# design.net
KiCad netlist of a schematic drawn in Altium Designer
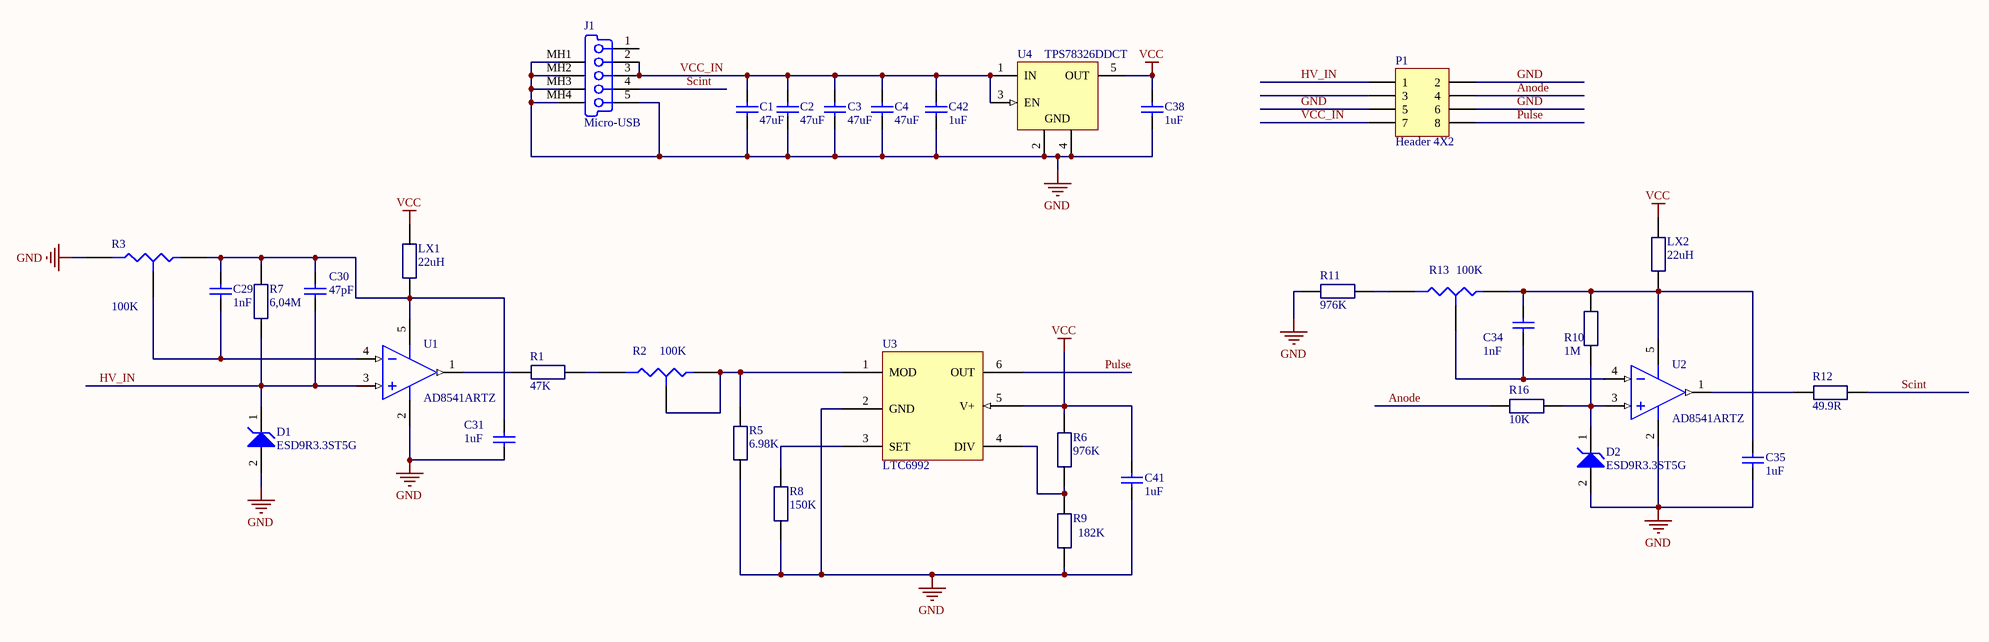
[diagram p0: Умножитель.SchDoc]

(export (version "E")
  (design (tool "Eeschema 10.0.6"))
  (components
    (comp (ref "C1")
      (value "47uF")
      (footprint "C1206")
      (description "Capacitor (Semiconductor SIM Model)")
      (fields (field (name "PUBLISHER") "Altium Limited"))
      (libsource (lib "Miscellaneous Devices") (part "Cap Semi"))
    )
    (comp (ref "C2")
      (value "47uF")
      (footprint "C1206")
      (description "Capacitor (Semiconductor SIM Model)")
      (fields (field (name "PUBLISHER") "Altium Limited"))
      (libsource (lib "Miscellaneous Devices") (part "Cap Semi"))
    )
    (comp (ref "C3")
      (value "47uF")
      (footprint "C1206")
      (description "Capacitor (Semiconductor SIM Model)")
      (fields (field (name "PUBLISHER") "Altium Limited"))
      (libsource (lib "Miscellaneous Devices") (part "Cap Semi"))
    )
    (comp (ref "C4")
      (value "47uF")
      (footprint "C1206")
      (description "Capacitor (Semiconductor SIM Model)")
      (fields (field (name "PUBLISHER") "Altium Limited"))
      (libsource (lib "Miscellaneous Devices") (part "Cap Semi"))
    )
    (comp (ref "C29")
      (value "1nF")
      (footprint "1608[0603]_CAP")
      (description "Capacitor (Semiconductor SIM Model)")
      (fields (field (name "PUBLISHER") "Altium Limited"))
      (libsource (lib "Miscellaneous Devices") (part "Cap Semi"))
    )
    (comp (ref "C30")
      (value "47pF")
      (footprint "1608[0603]_CAP")
      (description "Capacitor (Semiconductor SIM Model)")
      (fields (field (name "PUBLISHER") "Altium Limited"))
      (libsource (lib "Miscellaneous Devices") (part "Cap Semi"))
    )
    (comp (ref "C31")
      (value "1uF")
      (footprint "1608[0603]_CAP")
      (description "Capacitor (Semiconductor SIM Model)")
      (fields (field (name "PUBLISHER") "Altium Limited"))
      (libsource (lib "Miscellaneous Devices") (part "Cap Semi"))
    )
    (comp (ref "C34")
      (value "1nF")
      (footprint "1608[0603]_CAP")
      (description "Capacitor (Semiconductor SIM Model)")
      (fields (field (name "PUBLISHER") "Altium Limited"))
      (libsource (lib "Miscellaneous Devices") (part "Cap Semi"))
    )
    (comp (ref "C35")
      (value "1uF")
      (footprint "1608[0603]_CAP")
      (description "Capacitor (Semiconductor SIM Model)")
      (fields (field (name "PUBLISHER") "Altium Limited"))
      (libsource (lib "Miscellaneous Devices") (part "Cap Semi"))
    )
    (comp (ref "C38")
      (value "1uF")
      (footprint "1608[0603]_CAP")
      (description "Capacitor (Semiconductor SIM Model)")
      (fields (field (name "PUBLISHER") "Altium Limited"))
      (libsource (lib "Miscellaneous Devices") (part "Cap Semi"))
    )
    (comp (ref "C41")
      (value "1uF")
      (footprint "1608[0603]_CAP")
      (description "Capacitor (Semiconductor SIM Model)")
      (fields (field (name "PUBLISHER") "Altium Limited"))
      (libsource (lib "Miscellaneous Devices") (part "Cap Semi"))
    )
    (comp (ref "C42")
      (value "1uF")
      (footprint "1608[0603]_CAP")
      (description "Capacitor (Semiconductor SIM Model)")
      (fields (field (name "PUBLISHER") "Altium Limited"))
      (libsource (lib "Miscellaneous Devices") (part "Cap Semi"))
    )
    (comp (ref "D1")
      (value "ESD9R3.3ST5G")
      (footprint "ONSC-SOD-923-2-514AB-01_V")
      (fields (field (name "MANUFACTURER") "On Semiconductor"))
      (libsource (lib "ON Semi ESD Protection Diodes & Arrays") (part "ESD9R3.3ST5G"))
    )
    (comp (ref "D2")
      (value "ESD9R3.3ST5G")
      (footprint "ONSC-SOD-923-2-514AB-01_V")
      (fields (field (name "MANUFACTURER") "On Semiconductor"))
      (libsource (lib "ON Semi ESD Protection Diodes & Arrays") (part "ESD9R3.3ST5G"))
    )
    (comp (ref "J1")
      (value "Micro-USB")
      (footprint "47346-0001")
      (libsource (lib "Molex Serial Bus Mini USB") (part "0481900001"))
    )
    (comp (ref "LX1")
      (value "22uH")
      (footprint "Resistor")
      (libsource (lib "Микрон-3") (part "Resistor 0805"))
    )
    (comp (ref "LX2")
      (value "22uH")
      (footprint "Resistor")
      (libsource (lib "Микрон-3") (part "Resistor 0805"))
    )
    (comp (ref "P1")
      (value "Header 4X2")
      (footprint "PLS_FLAT_CONN")
      (description "Header, 4-Pin, Dual row")
      (fields (field (name "PUBLISHER") "Altium Limited"))
      (libsource (lib "Miscellaneous Connectors") (part "Header 4X2"))
    )
    (comp (ref "R1")
      (value "47K")
      (footprint "1608[0603]")
      (libsource (lib "Микрон-3") (part "Resistor 0805"))
    )
    (comp (ref "R2")
      (value "100K")
      (footprint "3223W")
      (description "Tapped Resistor")
      (fields (field (name "PUBLISHER") "Altium Limited"))
      (libsource (lib "Miscellaneous Devices") (part "Res Tap"))
    )
    (comp (ref "R3")
      (value "100K")
      (footprint "3223W")
      (description "Tapped Resistor")
      (fields (field (name "PUBLISHER") "Altium Limited"))
      (libsource (lib "Miscellaneous Devices") (part "Res Tap"))
    )
    (comp (ref "R5")
      (value "6.98K")
      (footprint "1608[0603]")
      (libsource (lib "Микрон-3") (part "Resistor 0805"))
    )
    (comp (ref "R6")
      (value "976K")
      (footprint "1608[0603]")
      (libsource (lib "Микрон-3") (part "Resistor 0805"))
    )
    (comp (ref "R7")
      (value "6,04M")
      (footprint "1608[0603]")
      (libsource (lib "Микрон-3") (part "Resistor 0805"))
    )
    (comp (ref "R8")
      (value "150K")
      (footprint "1608[0603]")
      (libsource (lib "Микрон-3") (part "Resistor 0805"))
    )
    (comp (ref "R9")
      (value "182K")
      (footprint "1608[0603]")
      (libsource (lib "Микрон-3") (part "Resistor 0805"))
    )
    (comp (ref "R10")
      (value "1M")
      (footprint "1608[0603]")
      (libsource (lib "Микрон-3") (part "Resistor 0805"))
    )
    (comp (ref "R11")
      (value "976K")
      (footprint "1608[0603]")
      (libsource (lib "Микрон-3") (part "Resistor 0805"))
    )
    (comp (ref "R12")
      (value "49.9R")
      (footprint "1608[0603]")
      (libsource (lib "Микрон-3") (part "Resistor 0805"))
    )
    (comp (ref "R13")
      (value "100K")
      (footprint "3223W")
      (description "Tapped Resistor")
      (fields (field (name "PUBLISHER") "Altium Limited"))
      (libsource (lib "Miscellaneous Devices") (part "Res Tap"))
    )
    (comp (ref "R16")
      (value "10K")
      (footprint "1608[0603]")
      (libsource (lib "Микрон-3") (part "Resistor 0805"))
    )
    (comp (ref "U1")
      (value "AD8541ARTZ")
      (footprint "ADI-RJ-5_N")
      (fields
        (field (name "GENERIC PART NUMBER") "AD8541")
        (field (name "MANUFACTURER") "Analog Devices")
        (field (name "PARTNUMBER") "AD8541ARTZ-R2")
      )
      (libsource (lib "Analog Devices Operational Amplifiers") (part "AD8541ARTZ-R2"))
    )
    (comp (ref "U2")
      (value "AD8541ARTZ")
      (footprint "ADI-RJ-5_N")
      (fields
        (field (name "GENERIC PART NUMBER") "AD8541")
        (field (name "MANUFACTURER") "Analog Devices")
        (field (name "PARTNUMBER") "AD8541ARTZ-R2")
      )
      (libsource (lib "Analog Devices Operational Amplifiers") (part "AD8541ARTZ-R2"))
    )
    (comp (ref "U3")
      (value "LTC6992")
      (footprint "SOT23-6L")
      (libsource (lib "My SCH library") (part "LTC6992"))
    )
    (comp (ref "U4")
      (value "TPS78326DDCT")
      (footprint "TI-DDC5_N")
      (fields (field (name "MANUFACTURER") "Texas Instruments"))
      (libsource (lib "TI Power Management Linear Regulator Single Channel LDO (0-350mA)") (part "TPS78330DDCR"))
    )
  )
  (nets
    (net (code "1") (name "/Anode") (class "Default")
      (node (ref "P1") (pin "4") (pinfunction "4_4") (pintype "passive"))
      (node (ref "R16") (pin "1") (pinfunction "A_1") (pintype "passive"))
    )
    (net (code "2") (name "/HV_IN") (class "Default")
      (node (ref "C30") (pin "2") (pinfunction "2_2") (pintype "passive"))
      (node (ref "D1") (pin "1") (pinfunction "K_1") (pintype "passive"))
      (node (ref "P1") (pin "1") (pinfunction "1_1") (pintype "passive"))
      (node (ref "R7") (pin "2") (pinfunction "2_2") (pintype "passive"))
      (node (ref "U1") (pin "3") (pinfunction "+IN_A_3") (pintype "input"))
    )
    (net (code "3") (name "/Pulse") (class "Default")
      (node (ref "P1") (pin "8") (pinfunction "8_8") (pintype "passive"))
      (node (ref "U3") (pin "6") (pinfunction "OUT_6") (pintype "power_in"))
    )
    (net (code "4") (name "/Scint") (class "Default")
      (node (ref "J1") (pin "4") (pinfunction "NC_4") (pintype "passive"))
      (node (ref "R12") (pin "1") (pinfunction "A_1") (pintype "passive"))
    )
    (net (code "5") (name "/VCC_IN") (class "Default")
      (node (ref "C1") (pin "1") (pinfunction "1_1") (pintype "passive"))
      (node (ref "C2") (pin "1") (pinfunction "1_1") (pintype "passive"))
      (node (ref "C3") (pin "1") (pinfunction "1_1") (pintype "passive"))
      (node (ref "C4") (pin "1") (pinfunction "1_1") (pintype "passive"))
      (node (ref "C42") (pin "1") (pinfunction "1_1") (pintype "passive"))
      (node (ref "J1") (pin "2") (pinfunction "D-_2") (pintype "passive"))
      (node (ref "J1") (pin "3") (pinfunction "D+_3") (pintype "passive"))
      (node (ref "P1") (pin "7") (pinfunction "7_7") (pintype "passive"))
      (node (ref "U4") (pin "1") (pinfunction "IN_1") (pintype "power_in"))
      (node (ref "U4") (pin "3") (pinfunction "EN_3") (pintype "input"))
    )
    (net (code "6") (name "GND") (class "Default")
      (node (ref "C1") (pin "2") (pinfunction "2_2") (pintype "passive"))
      (node (ref "C2") (pin "2") (pinfunction "2_2") (pintype "passive"))
      (node (ref "C3") (pin "2") (pinfunction "2_2") (pintype "passive"))
      (node (ref "C31") (pin "2") (pinfunction "2_2") (pintype "passive"))
      (node (ref "C35") (pin "2") (pinfunction "2_2") (pintype "passive"))
      (node (ref "C38") (pin "1") (pinfunction "1_1") (pintype "passive"))
      (node (ref "C4") (pin "2") (pinfunction "2_2") (pintype "passive"))
      (node (ref "C41") (pin "2") (pinfunction "2_2") (pintype "passive"))
      (node (ref "C42") (pin "2") (pinfunction "2_2") (pintype "passive"))
      (node (ref "D1") (pin "2") (pinfunction "A_2") (pintype "passive"))
      (node (ref "D2") (pin "2") (pinfunction "A_2") (pintype "passive"))
      (node (ref "J1") (pin "5") (pinfunction "GND_5") (pintype "passive"))
      (node (ref "J1") (pin "MH1") (pinfunction "Tab_MH1") (pintype "passive"))
      (node (ref "J1") (pin "MH2") (pinfunction "Tab_MH2") (pintype "passive"))
      (node (ref "J1") (pin "MH3") (pinfunction "Tab_MH3") (pintype "passive"))
      (node (ref "J1") (pin "MH4") (pinfunction "Tab_MH4") (pintype "passive"))
      (node (ref "P1") (pin "2") (pinfunction "2_2") (pintype "passive"))
      (node (ref "P1") (pin "5") (pinfunction "5_5") (pintype "passive"))
      (node (ref "P1") (pin "6") (pinfunction "6_6") (pintype "passive"))
      (node (ref "R11") (pin "1") (pinfunction "A_1") (pintype "passive"))
      (node (ref "R3") (pin "2") (pinfunction "B_2") (pintype "passive"))
      (node (ref "R5") (pin "2") (pinfunction "2_2") (pintype "passive"))
      (node (ref "R8") (pin "2") (pinfunction "2_2") (pintype "passive"))
      (node (ref "R9") (pin "2") (pinfunction "2_2") (pintype "passive"))
      (node (ref "U1") (pin "2") (pinfunction "-V_2") (pintype "power_in"))
      (node (ref "U2") (pin "2") (pinfunction "-V_2") (pintype "power_in"))
      (node (ref "U3") (pin "2") (pinfunction "GND_2") (pintype "passive"))
      (node (ref "U4") (pin "2") (pinfunction "GND_2") (pintype "power_in"))
      (node (ref "U4") (pin "4") (pinfunction "GND_4") (pintype "power_in"))
    )
    (net (code "7") (name "Net-(D2-K)") (class "Default")
      (node (ref "D2") (pin "1") (pinfunction "K_1") (pintype "passive"))
      (node (ref "R10") (pin "1") (pinfunction "A_1") (pintype "passive"))
      (node (ref "R16") (pin "2") (pinfunction "2_2") (pintype "passive"))
      (node (ref "U2") (pin "3") (pinfunction "+IN_A_3") (pintype "input"))
    )
    (net (code "8") (name "Net-(R1-A)") (class "Default")
      (node (ref "R1") (pin "1") (pinfunction "A_1") (pintype "passive"))
      (node (ref "R2") (pin "2") (pinfunction "B_2") (pintype "passive"))
    )
    (net (code "9") (name "Net-(R2-A)") (class "Default")
      (node (ref "R2") (pin "1") (pinfunction "A_1") (pintype "passive"))
      (node (ref "R2") (pin "3") (pinfunction "TAP_3") (pintype "passive"))
      (node (ref "R5") (pin "1") (pinfunction "A_1") (pintype "passive"))
      (node (ref "U3") (pin "1") (pinfunction "MOD_1") (pintype "passive"))
    )
    (net (code "10") (name "Net-(R3-A)") (class "Default")
      (node (ref "C29") (pin "1") (pinfunction "1_1") (pintype "passive"))
      (node (ref "C30") (pin "1") (pinfunction "1_1") (pintype "passive"))
      (node (ref "C31") (pin "1") (pinfunction "1_1") (pintype "passive"))
      (node (ref "LX1") (pin "2") (pinfunction "2_2") (pintype "passive"))
      (node (ref "R3") (pin "1") (pinfunction "A_1") (pintype "passive"))
      (node (ref "R7") (pin "1") (pinfunction "A_1") (pintype "passive"))
      (node (ref "U1") (pin "5") (pinfunction "+V_5") (pintype "power_in"))
    )
    (net (code "11") (name "Net-(R3-TAP)") (class "Default")
      (node (ref "C29") (pin "2") (pinfunction "2_2") (pintype "passive"))
      (node (ref "R3") (pin "3") (pinfunction "TAP_3") (pintype "passive"))
      (node (ref "U1") (pin "4") (pinfunction "-IN_A_4") (pintype "input"))
    )
    (net (code "12") (name "Net-(R8-A)") (class "Default")
      (node (ref "R8") (pin "1") (pinfunction "A_1") (pintype "passive"))
      (node (ref "U3") (pin "3") (pinfunction "SET_3") (pintype "power_in"))
    )
    (net (code "13") (name "Net-(R9-A)") (class "Default")
      (node (ref "R6") (pin "2") (pinfunction "2_2") (pintype "passive"))
      (node (ref "R9") (pin "1") (pinfunction "A_1") (pintype "passive"))
      (node (ref "U3") (pin "4") (pinfunction "DIV_4") (pintype "power_in"))
    )
    (net (code "14") (name "Net-(R13-A)") (class "Default")
      (node (ref "C34") (pin "1") (pinfunction "1_1") (pintype "passive"))
      (node (ref "C35") (pin "1") (pinfunction "1_1") (pintype "passive"))
      (node (ref "LX2") (pin "2") (pinfunction "2_2") (pintype "passive"))
      (node (ref "R10") (pin "2") (pinfunction "2_2") (pintype "passive"))
      (node (ref "R13") (pin "1") (pinfunction "A_1") (pintype "passive"))
      (node (ref "U2") (pin "5") (pinfunction "+V_5") (pintype "power_in"))
    )
    (net (code "15") (name "Net-(R13-B)") (class "Default")
      (node (ref "R11") (pin "2") (pinfunction "2_2") (pintype "passive"))
      (node (ref "R13") (pin "2") (pinfunction "B_2") (pintype "passive"))
    )
    (net (code "16") (name "Net-(R13-TAP)") (class "Default")
      (node (ref "C34") (pin "2") (pinfunction "2_2") (pintype "passive"))
      (node (ref "R13") (pin "3") (pinfunction "TAP_3") (pintype "passive"))
      (node (ref "U2") (pin "4") (pinfunction "-IN_A_4") (pintype "input"))
    )
    (net (code "17") (name "Net-(U1-OUT_A)") (class "Default")
      (node (ref "R1") (pin "2") (pinfunction "2_2") (pintype "passive"))
      (node (ref "U1") (pin "1") (pinfunction "OUT_A_1") (pintype "output"))
    )
    (net (code "18") (name "Net-(U2-OUT_A)") (class "Default")
      (node (ref "R12") (pin "2") (pinfunction "2_2") (pintype "passive"))
      (node (ref "U2") (pin "1") (pinfunction "OUT_A_1") (pintype "output"))
    )
    (net (code "19") (name "VCC") (class "Default")
      (node (ref "C38") (pin "2") (pinfunction "2_2") (pintype "passive"))
      (node (ref "C41") (pin "1") (pinfunction "1_1") (pintype "passive"))
      (node (ref "LX1") (pin "1") (pinfunction "A_1") (pintype "passive"))
      (node (ref "LX2") (pin "1") (pinfunction "A_1") (pintype "passive"))
      (node (ref "R6") (pin "1") (pinfunction "A_1") (pintype "passive"))
      (node (ref "U3") (pin "5") (pinfunction "V+_5") (pintype "input"))
      (node (ref "U4") (pin "5") (pinfunction "OUT_5") (pintype "power_in"))
    )
    (net (code "20") (name "unconnected-(J1-V_BUS_(5V)-Pad1)") (class "Default")
      (node (ref "J1") (pin "1") (pinfunction "V_BUS_(5V)_1") (pintype "passive"))
    )
    (net (code "21") (name "unconnected-(P1-Pad3)") (class "Default")
      (node (ref "P1") (pin "3") (pinfunction "3_3") (pintype "passive"))
    )
  )
)
